# Padawan_Shield_4.net
KiCad netlist of a schematic drawn in EAGLE
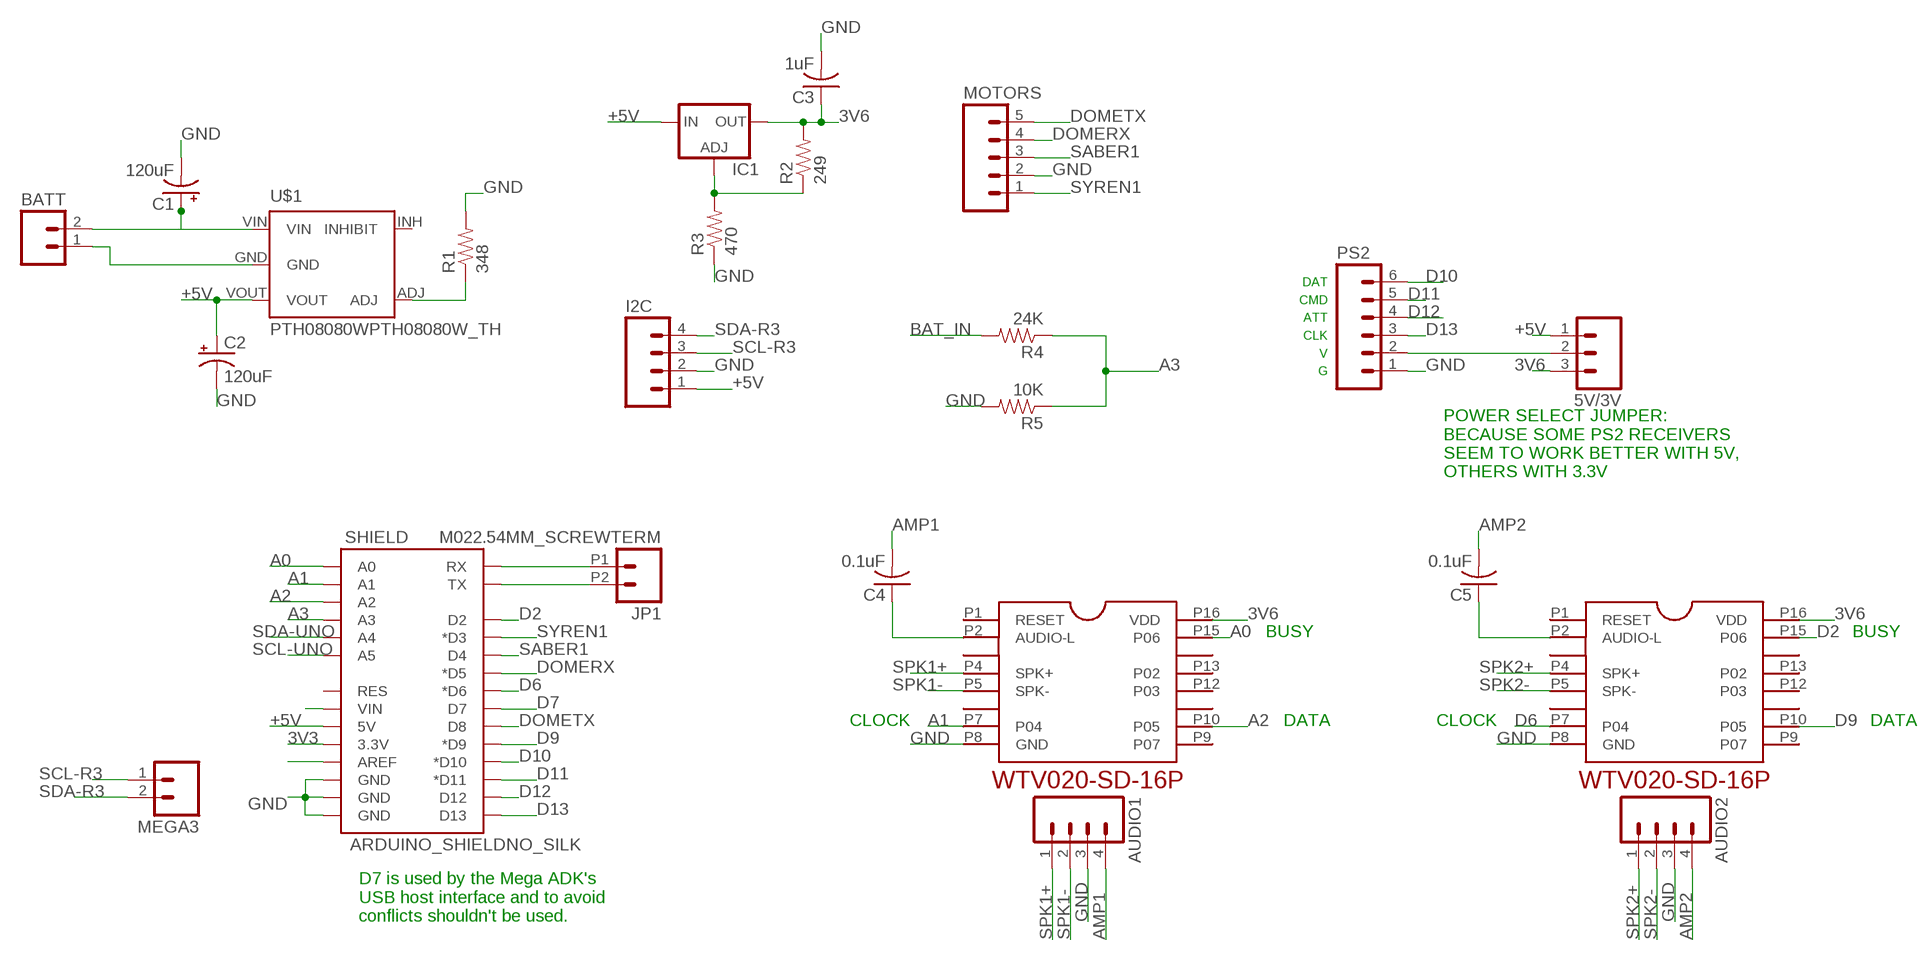
[diagram p0: schematic, sheet 1]

(export (version "E")
  (design (tool "Eeschema 10.0.6"))
  (components
    (comp (ref "5V/3V")
      (value "M03PTH")
      (footprint "eagle-import:1X03")
      (libsource (lib "eagle-import") (part "M03PTH"))
    )
    (comp (ref "AUDIO1")
      (value "M04PTH")
      (footprint "eagle-import:1X04")
      (libsource (lib "eagle-import") (part "M04PTH"))
    )
    (comp (ref "AUDIO2")
      (value "M04PTH")
      (footprint "eagle-import:1X04")
      (libsource (lib "eagle-import") (part "M04PTH"))
    )
    (comp (ref "BATT")
      (value "M02PTH")
      (footprint "eagle-import:1X02")
      (libsource (lib "eagle-import") (part "M02PTH"))
    )
    (comp (ref "C1")
      (value "120uF")
      (footprint "eagle-import:E2,5-6")
      (libsource (lib "eagle-import") (part "CPOL-USE2.5-6"))
    )
    (comp (ref "C2")
      (value "120uF")
      (footprint "eagle-import:E2,5-6")
      (libsource (lib "eagle-import") (part "CPOL-USE2.5-6"))
    )
    (comp (ref "C3")
      (value "1uF")
      (footprint "eagle-import:C025-030X050")
      (libsource (lib "eagle-import") (part "C-US025-030X050"))
    )
    (comp (ref "C4")
      (value "0.1uF")
      (footprint "eagle-import:C025-030X050")
      (libsource (lib "eagle-import") (part "C-US025-030X050"))
    )
    (comp (ref "C5")
      (value "0.1uF")
      (footprint "eagle-import:C025-030X050")
      (libsource (lib "eagle-import") (part "C-US025-030X050"))
    )
    (comp (ref "I2C")
      (value "M04PTH")
      (footprint "eagle-import:1X04")
      (libsource (lib "eagle-import") (part "M04PTH"))
    )
    (comp (ref "IC1")
      (value "LM317TS")
      (footprint "eagle-import:317TS")
      (libsource (lib "eagle-import") (part "LM317TS"))
    )
    (comp (ref "JP1")
      (value "M022.54MM_SCREWTERM")
      (footprint "eagle-import:1X02_2.54_SCREWTERM")
      (libsource (lib "eagle-import") (part "M022.54MM_SCREWTERM"))
    )
    (comp (ref "MEGA3")
      (value "M021X02_NO_SILK")
      (footprint "eagle-import:1X02_NO_SILK")
      (libsource (lib "eagle-import") (part "M021X02_NO_SILK"))
    )
    (comp (ref "MOTORS")
      (value "M05PTH")
      (footprint "eagle-import:1X05")
      (libsource (lib "eagle-import") (part "M05PTH"))
    )
    (comp (ref "PS2")
      (value "M06SILK_FEMALE_PTH")
      (footprint "eagle-import:1X06")
      (libsource (lib "eagle-import") (part "M06SILK_FEMALE_PTH"))
    )
    (comp (ref "R1")
      (value "348")
      (footprint "eagle-import:AXIAL-0.1EZ")
      (libsource (lib "eagle-import") (part "RESISTORPTH-1/4W-VERT-KIT"))
    )
    (comp (ref "R2")
      (value "249")
      (footprint "eagle-import:AXIAL-0.1EZ")
      (libsource (lib "eagle-import") (part "RESISTORPTH-1/4W-VERT-KIT"))
    )
    (comp (ref "R3")
      (value "470")
      (footprint "eagle-import:AXIAL-0.1EZ")
      (libsource (lib "eagle-import") (part "RESISTORPTH-1/4W-VERT-KIT"))
    )
    (comp (ref "R4")
      (value "24K")
      (footprint "eagle-import:AXIAL-0.1EZ")
      (libsource (lib "eagle-import") (part "RESISTORPTH-1/4W-VERT-KIT"))
    )
    (comp (ref "R5")
      (value "10K")
      (footprint "eagle-import:AXIAL-0.1EZ")
      (libsource (lib "eagle-import") (part "RESISTORPTH-1/4W-VERT-KIT"))
    )
    (comp (ref "SHIELD")
      (value "ARDUINO_SHIELDNO_SILK")
      (footprint "eagle-import:DUEMILANOVE_VIAS")
      (libsource (lib "eagle-import") (part "ARDUINO_SHIELDNO_SILK"))
    )
    (comp (ref "U$1")
      (value "PTH08080WPTH08080W_TH")
      (footprint "eagle-import:PTH08080W_TH")
      (libsource (lib "eagle-import") (part "PTH08080WPTH08080W_TH"))
    )
    (comp (ref "WTV1")
      (value "WTV020-SD-16P")
      (footprint "eagle-import:WTV020-16P")
      (libsource (lib "eagle-import") (part "WTV020-SD-16P"))
    )
    (comp (ref "WTV2")
      (value "WTV020-SD-16P")
      (footprint "eagle-import:WTV020-16P")
      (libsource (lib "eagle-import") (part "WTV020-SD-16P"))
    )
  )
  (nets
    (net (code "1") (name "/+5V") (class "Default")
      (node (ref "5V/3V") (pin "1") (pinfunction "1_1") (pintype "passive"))
      (node (ref "C2") (pin "+") (pinfunction "+_+") (pintype "passive"))
      (node (ref "I2C") (pin "1") (pinfunction "1_1") (pintype "passive"))
      (node (ref "IC1") (pin "3") (pinfunction "IN_3") (pintype "input"))
      (node (ref "SHIELD") (pin "5V") (pinfunction "5V_5V") (pintype "bidirectional"))
      (node (ref "U$1") (pin "VOUT") (pinfunction "VOUT_VOUT") (pintype "output"))
    )
    (net (code "2") (name "/3V3") (class "Default")
      (node (ref "SHIELD") (pin "3.3V") (pinfunction "3.3V_3.3V") (pintype "bidirectional"))
    )
    (net (code "3") (name "/3V6") (class "Default")
      (node (ref "5V/3V") (pin "3") (pinfunction "3_3") (pintype "passive"))
      (node (ref "C3") (pin "1") (pinfunction "1_1") (pintype "passive"))
      (node (ref "IC1") (pin "2") (pinfunction "OUT_2") (pintype "passive"))
      (node (ref "R2") (pin "P$2") (pinfunction "2_P$2") (pintype "passive"))
      (node (ref "WTV1") (pin "P16") (pinfunction "VDD_P16") (pintype "bidirectional"))
      (node (ref "WTV2") (pin "P16") (pinfunction "VDD_P16") (pintype "bidirectional"))
    )
    (net (code "4") (name "/A0") (class "Default")
      (node (ref "SHIELD") (pin "A0") (pinfunction "A0_A0") (pintype "bidirectional"))
      (node (ref "WTV1") (pin "P15") (pinfunction "P06_P15") (pintype "bidirectional"))
    )
    (net (code "5") (name "/A1") (class "Default")
      (node (ref "SHIELD") (pin "A1") (pinfunction "A1_A1") (pintype "bidirectional"))
      (node (ref "WTV1") (pin "P7") (pinfunction "P04_P7") (pintype "bidirectional"))
    )
    (net (code "6") (name "/A2") (class "Default")
      (node (ref "SHIELD") (pin "A2") (pinfunction "A2_A2") (pintype "bidirectional"))
      (node (ref "WTV1") (pin "P10") (pinfunction "P05_P10") (pintype "bidirectional"))
    )
    (net (code "7") (name "/A3") (class "Default")
      (node (ref "R4") (pin "P$1") (pinfunction "1_P$1") (pintype "passive"))
      (node (ref "R5") (pin "P$1") (pinfunction "1_P$1") (pintype "passive"))
      (node (ref "SHIELD") (pin "A3") (pinfunction "A3_A3") (pintype "bidirectional"))
    )
    (net (code "8") (name "/AMP1") (class "Default")
      (node (ref "AUDIO1") (pin "4") (pinfunction "4_4") (pintype "passive"))
      (node (ref "C4") (pin "2") (pinfunction "2_2") (pintype "passive"))
    )
    (net (code "9") (name "/AMP2") (class "Default")
      (node (ref "AUDIO2") (pin "4") (pinfunction "4_4") (pintype "passive"))
      (node (ref "C5") (pin "2") (pinfunction "2_2") (pintype "passive"))
    )
    (net (code "10") (name "/BAT_IN") (class "Default")
      (node (ref "BATT") (pin "2") (pinfunction "2_2") (pintype "passive"))
      (node (ref "C1") (pin "+") (pinfunction "+_+") (pintype "passive"))
      (node (ref "R4") (pin "P$2") (pinfunction "2_P$2") (pintype "passive"))
      (node (ref "U$1") (pin "VIN") (pinfunction "VIN_VIN") (pintype "input"))
    )
    (net (code "11") (name "/D2") (class "Default")
      (node (ref "SHIELD") (pin "D2") (pinfunction "D2_D2") (pintype "bidirectional"))
      (node (ref "WTV2") (pin "P15") (pinfunction "P06_P15") (pintype "bidirectional"))
    )
    (net (code "12") (name "/D6") (class "Default")
      (node (ref "SHIELD") (pin "D6") (pinfunction "*D6_D6") (pintype "bidirectional"))
      (node (ref "WTV2") (pin "P7") (pinfunction "P04_P7") (pintype "bidirectional"))
    )
    (net (code "13") (name "/D7") (class "Default")
      (node (ref "SHIELD") (pin "D7") (pinfunction "D7_D7") (pintype "bidirectional"))
    )
    (net (code "14") (name "/D9") (class "Default")
      (node (ref "SHIELD") (pin "D9") (pinfunction "*D9_D9") (pintype "bidirectional"))
      (node (ref "WTV2") (pin "P10") (pinfunction "P05_P10") (pintype "bidirectional"))
    )
    (net (code "15") (name "/D10") (class "Default")
      (node (ref "PS2") (pin "6") (pinfunction "6_6") (pintype "passive"))
      (node (ref "SHIELD") (pin "D10") (pinfunction "*D10_D10") (pintype "bidirectional"))
    )
    (net (code "16") (name "/D11") (class "Default")
      (node (ref "PS2") (pin "5") (pinfunction "5_5") (pintype "passive"))
      (node (ref "SHIELD") (pin "D11") (pinfunction "*D11_D11") (pintype "bidirectional"))
    )
    (net (code "17") (name "/D12") (class "Default")
      (node (ref "PS2") (pin "4") (pinfunction "4_4") (pintype "passive"))
      (node (ref "SHIELD") (pin "D12") (pinfunction "D12_D12") (pintype "bidirectional"))
    )
    (net (code "18") (name "/D13") (class "Default")
      (node (ref "PS2") (pin "3") (pinfunction "3_3") (pintype "passive"))
      (node (ref "SHIELD") (pin "D13") (pinfunction "D13_D13") (pintype "bidirectional"))
    )
    (net (code "19") (name "/DOMERX") (class "Default")
      (node (ref "MOTORS") (pin "4") (pinfunction "4_4") (pintype "passive"))
      (node (ref "SHIELD") (pin "D5") (pinfunction "*D5_D5") (pintype "bidirectional"))
    )
    (net (code "20") (name "/DOMETX") (class "Default")
      (node (ref "MOTORS") (pin "5") (pinfunction "5_5") (pintype "passive"))
      (node (ref "SHIELD") (pin "D8") (pinfunction "D8_D8") (pintype "bidirectional"))
    )
    (net (code "21") (name "/GND") (class "Default")
      (node (ref "AUDIO1") (pin "3") (pinfunction "3_3") (pintype "passive"))
      (node (ref "AUDIO2") (pin "3") (pinfunction "3_3") (pintype "passive"))
      (node (ref "BATT") (pin "1") (pinfunction "1_1") (pintype "passive"))
      (node (ref "C1") (pin "-") (pinfunction "-_-") (pintype "passive"))
      (node (ref "C2") (pin "-") (pinfunction "-_-") (pintype "passive"))
      (node (ref "C3") (pin "2") (pinfunction "2_2") (pintype "passive"))
      (node (ref "I2C") (pin "2") (pinfunction "2_2") (pintype "passive"))
      (node (ref "MOTORS") (pin "2") (pinfunction "2_2") (pintype "passive"))
      (node (ref "PS2") (pin "1") (pinfunction "1_1") (pintype "passive"))
      (node (ref "R1") (pin "P$2") (pinfunction "2_P$2") (pintype "passive"))
      (node (ref "R3") (pin "P$1") (pinfunction "1_P$1") (pintype "passive"))
      (node (ref "R5") (pin "P$2") (pinfunction "2_P$2") (pintype "passive"))
      (node (ref "SHIELD") (pin "GND@0") (pinfunction "GND_GND@0") (pintype "bidirectional"))
      (node (ref "SHIELD") (pin "GND@1") (pinfunction "GND_GND@1") (pintype "bidirectional"))
      (node (ref "SHIELD") (pin "GND@2") (pinfunction "GND_GND@2") (pintype "bidirectional"))
      (node (ref "U$1") (pin "GND") (pinfunction "GND_GND") (pintype "power_in"))
      (node (ref "WTV1") (pin "P8") (pinfunction "GND_P8") (pintype "bidirectional"))
      (node (ref "WTV2") (pin "P8") (pinfunction "GND_P8") (pintype "bidirectional"))
    )
    (net (code "22") (name "/SABER1") (class "Default")
      (node (ref "MOTORS") (pin "3") (pinfunction "3_3") (pintype "passive"))
      (node (ref "SHIELD") (pin "D4") (pinfunction "D4_D4") (pintype "bidirectional"))
    )
    (net (code "23") (name "/SCL-R3") (class "Default")
      (node (ref "I2C") (pin "3") (pinfunction "3_3") (pintype "passive"))
      (node (ref "MEGA3") (pin "1") (pinfunction "1_1") (pintype "passive"))
    )
    (net (code "24") (name "/SCL-UNO") (class "Default")
      (node (ref "SHIELD") (pin "A5") (pinfunction "A5_A5") (pintype "bidirectional"))
    )
    (net (code "25") (name "/SDA-R3") (class "Default")
      (node (ref "I2C") (pin "4") (pinfunction "4_4") (pintype "passive"))
      (node (ref "MEGA3") (pin "2") (pinfunction "2_2") (pintype "passive"))
    )
    (net (code "26") (name "/SDA-UNO") (class "Default")
      (node (ref "SHIELD") (pin "A4") (pinfunction "A4_A4") (pintype "bidirectional"))
    )
    (net (code "27") (name "/SPK1+") (class "Default")
      (node (ref "AUDIO1") (pin "1") (pinfunction "1_1") (pintype "passive"))
      (node (ref "WTV1") (pin "P4") (pinfunction "SPK+_P4") (pintype "bidirectional"))
    )
    (net (code "28") (name "/SPK1-") (class "Default")
      (node (ref "AUDIO1") (pin "2") (pinfunction "2_2") (pintype "passive"))
      (node (ref "WTV1") (pin "P5") (pinfunction "SPK-_P5") (pintype "bidirectional"))
    )
    (net (code "29") (name "/SPK2+") (class "Default")
      (node (ref "AUDIO2") (pin "1") (pinfunction "1_1") (pintype "passive"))
      (node (ref "WTV2") (pin "P4") (pinfunction "SPK+_P4") (pintype "bidirectional"))
    )
    (net (code "30") (name "/SPK2-") (class "Default")
      (node (ref "AUDIO2") (pin "2") (pinfunction "2_2") (pintype "passive"))
      (node (ref "WTV2") (pin "P5") (pinfunction "SPK-_P5") (pintype "bidirectional"))
    )
    (net (code "31") (name "/SYREN1") (class "Default")
      (node (ref "MOTORS") (pin "1") (pinfunction "1_1") (pintype "passive"))
      (node (ref "SHIELD") (pin "D3") (pinfunction "*D3_D3") (pintype "bidirectional"))
    )
    (net (code "32") (name "Net-(5V/3V-Pad2)") (class "Default")
      (node (ref "5V/3V") (pin "2") (pinfunction "2_2") (pintype "passive"))
      (node (ref "PS2") (pin "2") (pinfunction "2_2") (pintype "passive"))
    )
    (net (code "33") (name "Net-(IC1-ADJ)") (class "Default")
      (node (ref "IC1") (pin "1") (pinfunction "ADJ_1") (pintype "input"))
      (node (ref "R2") (pin "P$1") (pinfunction "1_P$1") (pintype "passive"))
      (node (ref "R3") (pin "P$2") (pinfunction "2_P$2") (pintype "passive"))
    )
    (net (code "34") (name "Net-(JP1-1)") (class "Default")
      (node (ref "JP1") (pin "P1") (pinfunction "1_P1") (pintype "passive"))
      (node (ref "SHIELD") (pin "RX") (pinfunction "RX_RX") (pintype "bidirectional"))
    )
    (net (code "35") (name "Net-(JP1-2)") (class "Default")
      (node (ref "JP1") (pin "P2") (pinfunction "2_P2") (pintype "passive"))
      (node (ref "SHIELD") (pin "TX") (pinfunction "TX_TX") (pintype "bidirectional"))
    )
    (net (code "36") (name "Net-(R1-1)") (class "Default")
      (node (ref "R1") (pin "P$1") (pinfunction "1_P$1") (pintype "passive"))
      (node (ref "U$1") (pin "ADJ") (pinfunction "ADJ_ADJ") (pintype "input"))
    )
    (net (code "37") (name "Net-(WTV1-AUDIO-L)") (class "Default")
      (node (ref "C4") (pin "1") (pinfunction "1_1") (pintype "passive"))
      (node (ref "WTV1") (pin "P2") (pinfunction "AUDIO-L_P2") (pintype "bidirectional"))
    )
    (net (code "38") (name "Net-(WTV2-AUDIO-L)") (class "Default")
      (node (ref "C5") (pin "1") (pinfunction "1_1") (pintype "passive"))
      (node (ref "WTV2") (pin "P2") (pinfunction "AUDIO-L_P2") (pintype "bidirectional"))
    )
    (net (code "39") (name "unconnected-(SHIELD-PadAREF)") (class "Default")
      (node (ref "SHIELD") (pin "AREF") (pinfunction "AREF_AREF") (pintype "bidirectional"))
    )
    (net (code "40") (name "unconnected-(SHIELD-PadRES)") (class "Default")
      (node (ref "SHIELD") (pin "RES") (pinfunction "RES_RES") (pintype "bidirectional"))
    )
    (net (code "41") (name "unconnected-(SHIELD-PadVIN)") (class "Default")
      (node (ref "SHIELD") (pin "VIN") (pinfunction "VIN_VIN") (pintype "bidirectional"))
    )
    (net (code "42") (name "unconnected-(U$1-INHIBIT-PadINH)") (class "Default")
      (node (ref "U$1") (pin "INH") (pinfunction "INHIBIT_INH") (pintype "input"))
    )
    (net (code "43") (name "unconnected-(WTV1-P02-PadP13)") (class "Default")
      (node (ref "WTV1") (pin "P13") (pinfunction "P02_P13") (pintype "bidirectional"))
    )
    (net (code "44") (name "unconnected-(WTV1-P03-PadP12)") (class "Default")
      (node (ref "WTV1") (pin "P12") (pinfunction "P03_P12") (pintype "bidirectional"))
    )
    (net (code "45") (name "unconnected-(WTV1-P07-PadP9)") (class "Default")
      (node (ref "WTV1") (pin "P9") (pinfunction "P07_P9") (pintype "bidirectional"))
    )
    (net (code "46") (name "unconnected-(WTV1-RESET-PadP1)") (class "Default")
      (node (ref "WTV1") (pin "P1") (pinfunction "RESET_P1") (pintype "bidirectional"))
    )
    (net (code "47") (name "unconnected-(WTV2-P02-PadP13)") (class "Default")
      (node (ref "WTV2") (pin "P13") (pinfunction "P02_P13") (pintype "bidirectional"))
    )
    (net (code "48") (name "unconnected-(WTV2-P03-PadP12)") (class "Default")
      (node (ref "WTV2") (pin "P12") (pinfunction "P03_P12") (pintype "bidirectional"))
    )
    (net (code "49") (name "unconnected-(WTV2-P07-PadP9)") (class "Default")
      (node (ref "WTV2") (pin "P9") (pinfunction "P07_P9") (pintype "bidirectional"))
    )
    (net (code "50") (name "unconnected-(WTV2-RESET-PadP1)") (class "Default")
      (node (ref "WTV2") (pin "P1") (pinfunction "RESET_P1") (pintype "bidirectional"))
    )
  )
)
